# kul_rev0.net
KiCad netlist of a schematic drawn in EAGLE
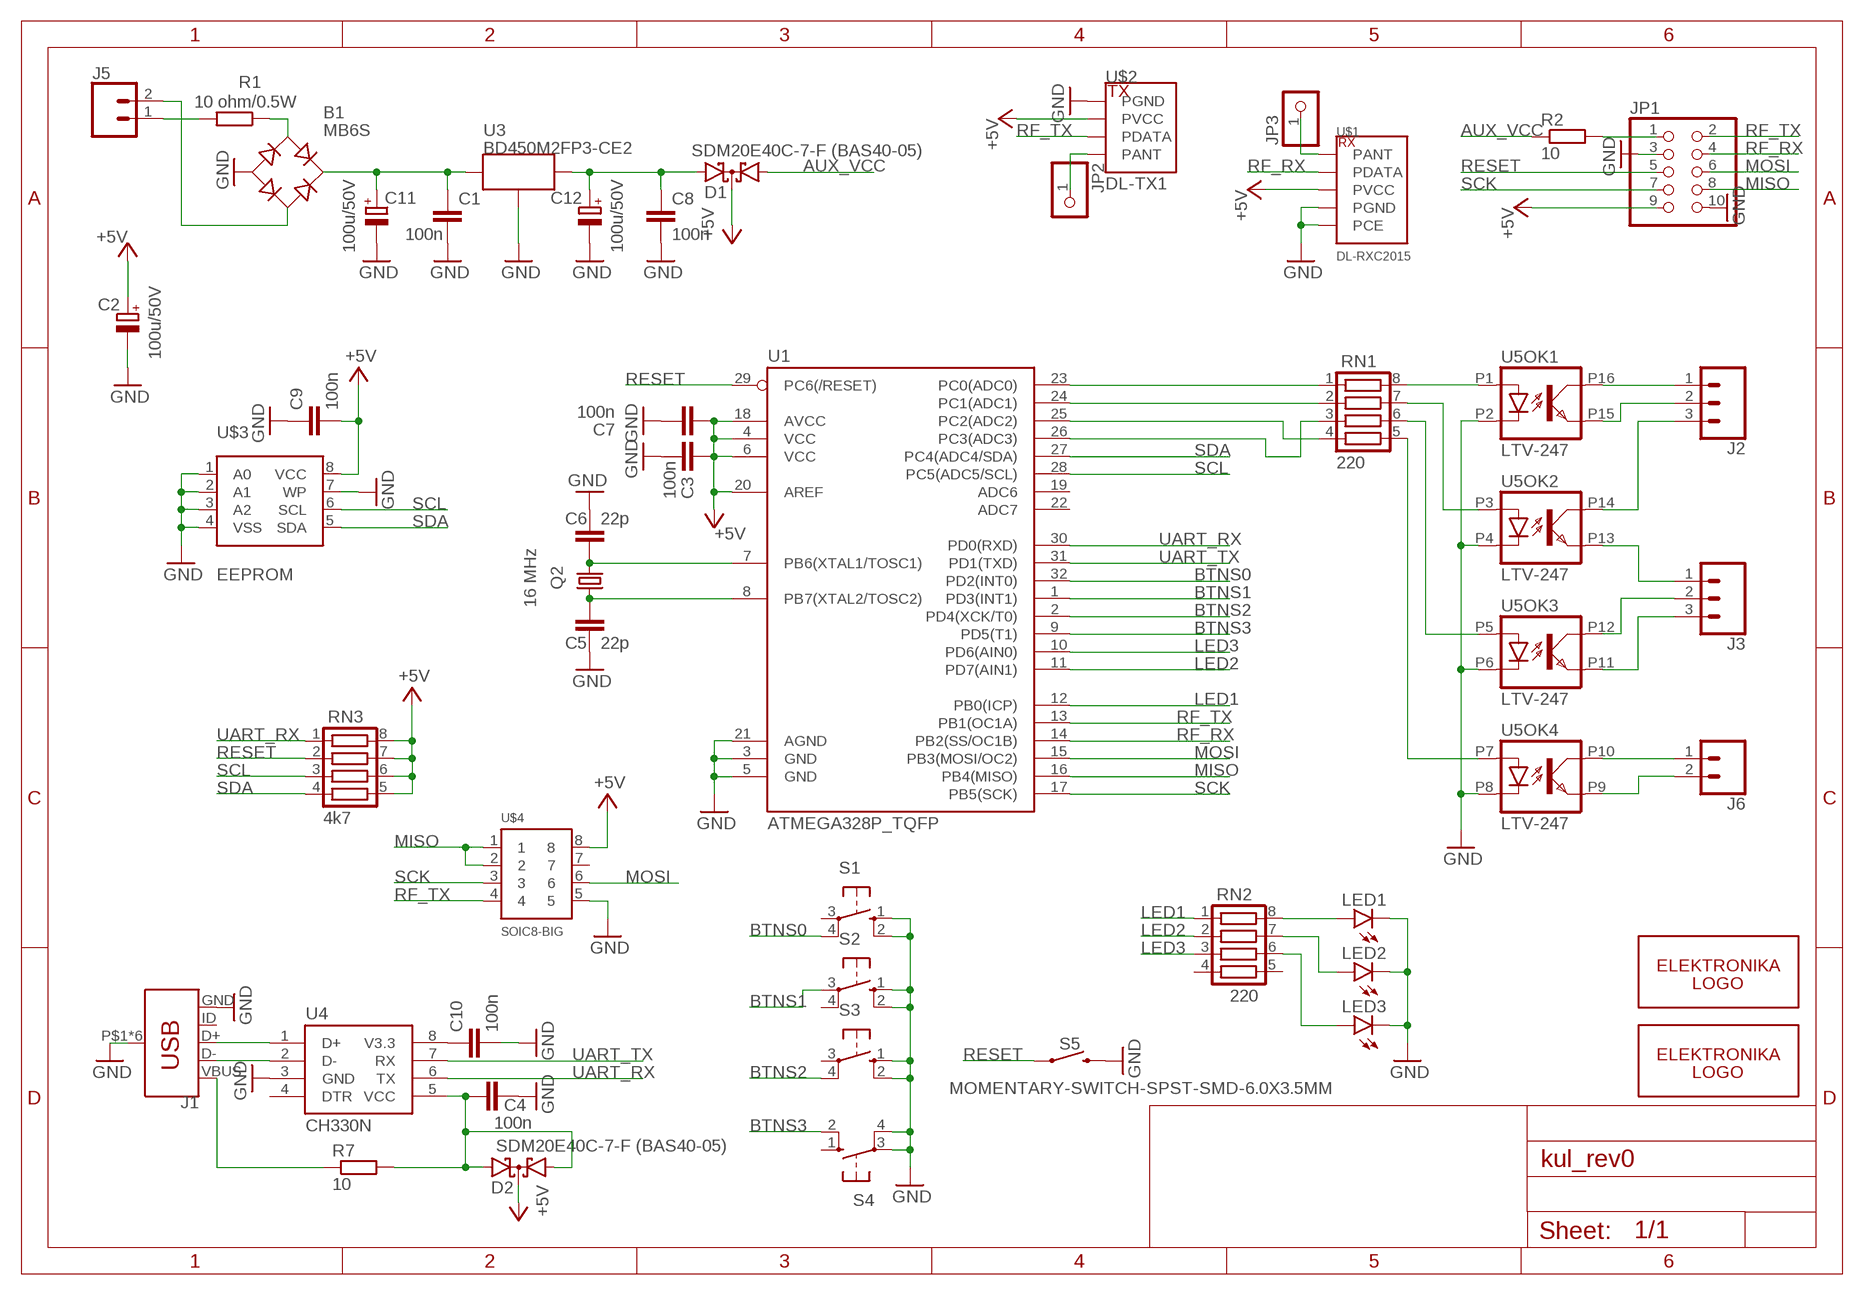
[diagram p0: schematic, sheet 1]

(export (version "E")
  (design (tool "Eeschema 10.0.6"))
  (components
    (comp (ref "B1")
      (value "MB6S")
      (footprint "eagle-import:SOIC-4")
      (libsource (lib "eagle-import") (part "MBS6"))
    )
    (comp (ref "C1")
      (value "100n")
      (footprint "eagle-import:C0603")
      (libsource (lib "eagle-import") (part "C-EUC0603"))
    )
    (comp (ref "C2")
      (value "100u/50V")
      (footprint "eagle-import:E5-6")
      (libsource (lib "eagle-import") (part "CPOL-EUE5-6"))
    )
    (comp (ref "C3")
      (value "100n")
      (footprint "eagle-import:C0603")
      (libsource (lib "eagle-import") (part "C-EUC0603"))
    )
    (comp (ref "C4")
      (value "100n")
      (footprint "eagle-import:C0603")
      (libsource (lib "eagle-import") (part "C-EUC0603"))
    )
    (comp (ref "C5")
      (value "22p")
      (footprint "eagle-import:C0603")
      (libsource (lib "eagle-import") (part "C-EUC0603"))
    )
    (comp (ref "C6")
      (value "22p")
      (footprint "eagle-import:C0603")
      (libsource (lib "eagle-import") (part "C-EUC0603"))
    )
    (comp (ref "C7")
      (value "100n")
      (footprint "eagle-import:C0603")
      (libsource (lib "eagle-import") (part "C-EUC0603"))
    )
    (comp (ref "C8")
      (value "100n")
      (footprint "eagle-import:C0603")
      (libsource (lib "eagle-import") (part "C-EUC0603"))
    )
    (comp (ref "C9")
      (value "100n")
      (footprint "eagle-import:C0603")
      (libsource (lib "eagle-import") (part "C-EUC0603"))
    )
    (comp (ref "C10")
      (value "100n")
      (footprint "eagle-import:C0603")
      (libsource (lib "eagle-import") (part "C-EUC0603"))
    )
    (comp (ref "C11")
      (value "100u/50V")
      (footprint "eagle-import:E5-6")
      (libsource (lib "eagle-import") (part "CPOL-EUE5-6"))
    )
    (comp (ref "C12")
      (value "100u/50V")
      (footprint "eagle-import:E5-6")
      (libsource (lib "eagle-import") (part "CPOL-EUE5-6"))
    )
    (comp (ref "D1")
      (value "SDM20E40C-7-F (BAS40-05)")
      (footprint "eagle-import:SOT23")
      (libsource (lib "eagle-import") (part "BAS40-05"))
    )
    (comp (ref "D2")
      (value "SDM20E40C-7-F (BAS40-05)")
      (footprint "eagle-import:SOT23")
      (libsource (lib "eagle-import") (part "BAS40-05"))
    )
    (comp (ref "J1")
      (value "USB_MICRO-BLCSC")
      (footprint "eagle-import:C40951_USB")
      (libsource (lib "eagle-import") (part "USB_MICRO-BLCSC"))
    )
    (comp (ref "J2")
      (value "CONN_03SCREW_LOCK")
      (footprint "eagle-import:SCREWTERMINAL-3.5MM-3_LOCK.007S")
      (libsource (lib "eagle-import") (part "CONN_03SCREW_LOCK"))
    )
    (comp (ref "J3")
      (value "CONN_03SCREW_LOCK")
      (footprint "eagle-import:SCREWTERMINAL-3.5MM-3_LOCK.007S")
      (libsource (lib "eagle-import") (part "CONN_03SCREW_LOCK"))
    )
    (comp (ref "J5")
      (value "CONN_023.5MM")
      (footprint "eagle-import:SCREWTERMINAL-3.5MM-2")
      (libsource (lib "eagle-import") (part "CONN_023.5MM"))
    )
    (comp (ref "J6")
      (value "CONN_023.5MM")
      (footprint "eagle-import:SCREWTERMINAL-3.5MM-2")
      (libsource (lib "eagle-import") (part "CONN_023.5MM"))
    )
    (comp (ref "JP1")
      (value "PINHD-2X5")
      (footprint "eagle-import:2X05")
      (libsource (lib "eagle-import") (part "PINHD-2X5"))
    )
    (comp (ref "JP2")
      (value "PINHD-1X1")
      (footprint "eagle-import:1X01")
      (libsource (lib "eagle-import") (part "PINHD-1X1"))
    )
    (comp (ref "JP3")
      (value "PINHD-1X1")
      (footprint "eagle-import:1X01")
      (libsource (lib "eagle-import") (part "PINHD-1X1"))
    )
    (comp (ref "LED1")
      (value "LEDCHIP-LED0805")
      (footprint "eagle-import:CHIP-LED0805")
      (libsource (lib "eagle-import") (part "LEDCHIP-LED0805"))
    )
    (comp (ref "LED2")
      (value "LEDCHIP-LED0805")
      (footprint "eagle-import:CHIP-LED0805")
      (libsource (lib "eagle-import") (part "LEDCHIP-LED0805"))
    )
    (comp (ref "LED3")
      (value "LEDCHIP-LED0805")
      (footprint "eagle-import:CHIP-LED0805")
      (libsource (lib "eagle-import") (part "LEDCHIP-LED0805"))
    )
    (comp (ref "Q2")
      (value "16 MHz")
      (footprint "eagle-import:3.2X2.5_KX-7")
      (libsource (lib "eagle-import") (part "KX-7"))
    )
    (comp (ref "R1")
      (value "10 ohm/0.5W")
      (footprint "eagle-import:R0805")
      (libsource (lib "eagle-import") (part "R-EU_R0805"))
    )
    (comp (ref "R2")
      (value "10")
      (footprint "eagle-import:R0603")
      (libsource (lib "eagle-import") (part "R-EU_R0603"))
    )
    (comp (ref "R7")
      (value "10")
      (footprint "eagle-import:R0603")
      (libsource (lib "eagle-import") (part "R-EU_R0603"))
    )
    (comp (ref "RN1")
      (value "220")
      (footprint "eagle-import:CTS742C083")
      (libsource (lib "eagle-import") (part "CTS742C083"))
    )
    (comp (ref "RN2")
      (value "220")
      (footprint "eagle-import:CTS742C083")
      (libsource (lib "eagle-import") (part "CTS742C083"))
    )
    (comp (ref "RN3")
      (value "4k7")
      (footprint "eagle-import:CTS742C083")
      (libsource (lib "eagle-import") (part "CTS742C083"))
    )
    (comp (ref "S1")
      (value "10-XX")
      (footprint "eagle-import:B3F-10XX")
      (fields (field (name "MPN") "B3F-1000"))
      (libsource (lib "eagle-import") (part "10-XX"))
    )
    (comp (ref "S2")
      (value "10-XX")
      (footprint "eagle-import:B3F-10XX")
      (fields (field (name "MPN") "B3F-1000"))
      (libsource (lib "eagle-import") (part "10-XX"))
    )
    (comp (ref "S3")
      (value "10-XX")
      (footprint "eagle-import:B3F-10XX")
      (fields (field (name "MPN") "B3F-1000"))
      (libsource (lib "eagle-import") (part "10-XX"))
    )
    (comp (ref "S4")
      (value "10-XX")
      (footprint "eagle-import:B3F-10XX")
      (fields (field (name "MPN") "B3F-1000"))
      (libsource (lib "eagle-import") (part "10-XX"))
    )
    (comp (ref "S5")
      (value "MOMENTARY-SWITCH-SPST-SMD-6.0X3.5MM")
      (footprint "eagle-import:TACTILE_SWITCH_SMD_6.0X3.5MM")
      (libsource (lib "eagle-import") (part "MOMENTARY-SWITCH-SPST-SMD-6.0X3.5MM"))
    )
    (comp (ref "U$1")
      (value "DL-RXC2015")
      (footprint "eagle-import:DL-RXC2015")
      (libsource (lib "eagle-import") (part "DL-RXC2015"))
    )
    (comp (ref "U$2")
      (value "DL-TX1")
      (footprint "eagle-import:DL-TX1")
      (libsource (lib "eagle-import") (part "DL-TX1"))
    )
    (comp (ref "U$3")
      (value "EEPROM")
      (footprint "eagle-import:SOIC8")
      (libsource (lib "eagle-import") (part "EEPROM"))
    )
    (comp (ref "U$4")
      (value "SOIC8-BIG")
      (footprint "eagle-import:SOIC8_BIG")
      (libsource (lib "eagle-import") (part "SOIC8-BIG"))
    )
    (comp (ref "U$5")
      (value "ELEKTRONIKA_BA_ELEBA_LOGO-121")
      (footprint "eagle-import:ELEKTRONIKA_BA_ELEBALOGO_ELEBALOGO_B_121")
      (libsource (lib "eagle-import") (part "ELEKTRONIKA_BA_ELEBA_LOGO-121"))
    )
    (comp (ref "U$6")
      (value "ELEKTRONIKA_BA_ELEBA_LOGO")
      (footprint "eagle-import:ELEKTRONIKA_BA_ELEBALOGO_ELEBALOGO_B_122")
      (libsource (lib "eagle-import") (part "ELEKTRONIKA_BA_ELEBA_LOGO"))
    )
    (comp (ref "U1")
      (value "ATMEGA328P_TQFP")
      (footprint "eagle-import:TQFP32-08")
      (libsource (lib "eagle-import") (part "ATMEGA328P_TQFP"))
    )
    (comp (ref "U3")
      (value "BD450M2FP3-CE2")
      (footprint "eagle-import:C308597_LDO")
      (libsource (lib "eagle-import") (part "C308597_LDO"))
    )
    (comp (ref "U4")
      (value "CH330N")
      (footprint "eagle-import:SOIC8")
      (libsource (lib "eagle-import") (part "CH330N"))
    )
    (comp (ref "U5")
      (value "LTV-247")
      (footprint "eagle-import:SOP-16_4.4MM")
      (libsource (lib "eagle-import") (part "LTV-247"))
    )
  )
  (nets
    (net (code "1") (name "+5V") (class "Default")
      (node (ref "C2") (pin "+") (pinfunction "+_+") (pintype "passive"))
      (node (ref "C3") (pin "2") (pinfunction "2_2") (pintype "passive"))
      (node (ref "C7") (pin "2") (pinfunction "2_2") (pintype "passive"))
      (node (ref "C9") (pin "2") (pinfunction "2_2") (pintype "passive"))
      (node (ref "D1") (pin "3") (pinfunction "C_3") (pintype "passive"))
      (node (ref "D2") (pin "3") (pinfunction "C_3") (pintype "passive"))
      (node (ref "JP1") (pin "9") (pinfunction "9_9") (pintype "passive"))
      (node (ref "RN3") (pin "5") (pinfunction "5_5") (pintype "passive"))
      (node (ref "RN3") (pin "6") (pinfunction "6_6") (pintype "passive"))
      (node (ref "RN3") (pin "7") (pinfunction "7_7") (pintype "passive"))
      (node (ref "RN3") (pin "8") (pinfunction "8_8") (pintype "passive"))
      (node (ref "U$1") (pin "PVCC") (pinfunction "PVCC_PVCC") (pintype "power_in"))
      (node (ref "U$2") (pin "PVDD") (pinfunction "PVCC_PVDD") (pintype "power_in"))
      (node (ref "U$3") (pin "8") (pinfunction "VCC_8") (pintype "bidirectional"))
      (node (ref "U$4") (pin "8") (pinfunction "8_8") (pintype "bidirectional"))
      (node (ref "U1") (pin "18") (pinfunction "AVCC_18") (pintype "bidirectional"))
      (node (ref "U1") (pin "20") (pinfunction "AREF_20") (pintype "bidirectional"))
      (node (ref "U1") (pin "4") (pinfunction "VCC_4") (pintype "bidirectional"))
      (node (ref "U1") (pin "6") (pinfunction "VCC_6") (pintype "bidirectional"))
    )
    (net (code "2") (name "/AUX_VCC") (class "Default")
      (node (ref "D1") (pin "1") (pinfunction "A1_1") (pintype "passive"))
      (node (ref "R2") (pin "1") (pinfunction "1_1") (pintype "passive"))
    )
    (net (code "3") (name "/BTNS0") (class "Default")
      (node (ref "S1") (pin "4") (pinfunction "P1_4") (pintype "passive"))
      (node (ref "U1") (pin "32") (pinfunction "PD2(INT0)_32") (pintype "bidirectional"))
    )
    (net (code "4") (name "/BTNS1") (class "Default")
      (node (ref "S2") (pin "3") (pinfunction "P_3") (pintype "passive"))
      (node (ref "U1") (pin "1") (pinfunction "PD3(INT1)_1") (pintype "bidirectional"))
    )
    (net (code "5") (name "/BTNS2") (class "Default")
      (node (ref "S3") (pin "4") (pinfunction "P1_4") (pintype "passive"))
      (node (ref "U1") (pin "2") (pinfunction "PD4(XCK/T0)_2") (pintype "bidirectional"))
    )
    (net (code "6") (name "/BTNS3") (class "Default")
      (node (ref "S4") (pin "2") (pinfunction "S1_2") (pintype "passive"))
      (node (ref "U1") (pin "9") (pinfunction "PD5(T1)_9") (pintype "bidirectional"))
    )
    (net (code "7") (name "/LED1") (class "Default")
      (node (ref "RN2") (pin "1") (pinfunction "1_1") (pintype "passive"))
      (node (ref "U1") (pin "12") (pinfunction "PB0(ICP)_12") (pintype "bidirectional"))
    )
    (net (code "8") (name "/LED2") (class "Default")
      (node (ref "RN2") (pin "2") (pinfunction "2_2") (pintype "passive"))
      (node (ref "U1") (pin "11") (pinfunction "PD7(AIN1)_11") (pintype "bidirectional"))
    )
    (net (code "9") (name "/LED3") (class "Default")
      (node (ref "RN2") (pin "3") (pinfunction "3_3") (pintype "passive"))
      (node (ref "U1") (pin "10") (pinfunction "PD6(AIN0)_10") (pintype "bidirectional"))
    )
    (net (code "10") (name "/MISO") (class "Default")
      (node (ref "JP1") (pin "8") (pinfunction "8_8") (pintype "passive"))
      (node (ref "U$4") (pin "1") (pinfunction "1_1") (pintype "bidirectional"))
      (node (ref "U$4") (pin "2") (pinfunction "2_2") (pintype "bidirectional"))
      (node (ref "U1") (pin "16") (pinfunction "PB4(MISO)_16") (pintype "bidirectional"))
    )
    (net (code "11") (name "/MOSI") (class "Default")
      (node (ref "JP1") (pin "6") (pinfunction "6_6") (pintype "passive"))
      (node (ref "U$4") (pin "6") (pinfunction "6_6") (pintype "bidirectional"))
      (node (ref "U1") (pin "15") (pinfunction "PB3(MOSI/OC2)_15") (pintype "bidirectional"))
    )
    (net (code "12") (name "/RESET") (class "Default")
      (node (ref "JP1") (pin "5") (pinfunction "5_5") (pintype "passive"))
      (node (ref "RN3") (pin "2") (pinfunction "2_2") (pintype "passive"))
      (node (ref "S5") (pin "1") (pinfunction "1_1") (pintype "passive"))
      (node (ref "U1") (pin "29") (pinfunction "PC6(/RESET)_29") (pintype "bidirectional"))
    )
    (net (code "13") (name "/RF_RX") (class "Default")
      (node (ref "JP1") (pin "4") (pinfunction "4_4") (pintype "passive"))
      (node (ref "U$1") (pin "PDATA") (pinfunction "PDATA_PDATA") (pintype "output"))
      (node (ref "U1") (pin "14") (pinfunction "PB2(SS/OC1B)_14") (pintype "bidirectional"))
    )
    (net (code "14") (name "/RF_TX") (class "Default")
      (node (ref "JP1") (pin "2") (pinfunction "2_2") (pintype "passive"))
      (node (ref "U$2") (pin "PDATA") (pinfunction "PDATA_PDATA") (pintype "input"))
      (node (ref "U$4") (pin "4") (pinfunction "4_4") (pintype "bidirectional"))
      (node (ref "U1") (pin "13") (pinfunction "PB1(OC1A)_13") (pintype "bidirectional"))
    )
    (net (code "15") (name "/SCK") (class "Default")
      (node (ref "JP1") (pin "7") (pinfunction "7_7") (pintype "passive"))
      (node (ref "U$4") (pin "3") (pinfunction "3_3") (pintype "bidirectional"))
      (node (ref "U1") (pin "17") (pinfunction "PB5(SCK)_17") (pintype "bidirectional"))
    )
    (net (code "16") (name "/SCL") (class "Default")
      (node (ref "RN3") (pin "3") (pinfunction "3_3") (pintype "passive"))
      (node (ref "U$3") (pin "6") (pinfunction "SCL_6") (pintype "bidirectional"))
      (node (ref "U1") (pin "28") (pinfunction "PC5(ADC5/SCL)_28") (pintype "bidirectional"))
    )
    (net (code "17") (name "/SDA") (class "Default")
      (node (ref "RN3") (pin "4") (pinfunction "4_4") (pintype "passive"))
      (node (ref "U$3") (pin "5") (pinfunction "SDA_5") (pintype "bidirectional"))
      (node (ref "U1") (pin "27") (pinfunction "PC4(ADC4/SDA)_27") (pintype "bidirectional"))
    )
    (net (code "18") (name "/UART_RX") (class "Default")
      (node (ref "RN3") (pin "1") (pinfunction "1_1") (pintype "passive"))
      (node (ref "U1") (pin "30") (pinfunction "PD0(RXD)_30") (pintype "bidirectional"))
      (node (ref "U4") (pin "6") (pinfunction "TX_6") (pintype "output"))
    )
    (net (code "19") (name "/UART_TX") (class "Default")
      (node (ref "U1") (pin "31") (pinfunction "PD1(TXD)_31") (pintype "bidirectional"))
      (node (ref "U4") (pin "7") (pinfunction "RX_7") (pintype "input"))
    )
    (net (code "20") (name "GND") (class "Default")
      (node (ref "B1") (pin "-") (pinfunction "-_-") (pintype "passive"))
      (node (ref "C1") (pin "2") (pinfunction "2_2") (pintype "passive"))
      (node (ref "C10") (pin "2") (pinfunction "2_2") (pintype "passive"))
      (node (ref "C11") (pin "-") (pinfunction "-_-") (pintype "passive"))
      (node (ref "C12") (pin "-") (pinfunction "-_-") (pintype "passive"))
      (node (ref "C2") (pin "-") (pinfunction "-_-") (pintype "passive"))
      (node (ref "C3") (pin "1") (pinfunction "1_1") (pintype "passive"))
      (node (ref "C4") (pin "2") (pinfunction "2_2") (pintype "passive"))
      (node (ref "C5") (pin "2") (pinfunction "2_2") (pintype "passive"))
      (node (ref "C6") (pin "1") (pinfunction "1_1") (pintype "passive"))
      (node (ref "C7") (pin "1") (pinfunction "1_1") (pintype "passive"))
      (node (ref "C8") (pin "2") (pinfunction "2_2") (pintype "passive"))
      (node (ref "C9") (pin "1") (pinfunction "1_1") (pintype "passive"))
      (node (ref "J1") (pin "GND") (pinfunction "GND_GND") (pintype "power_in"))
      (node (ref "J1") (pin "P$1") (pinfunction "SHIELD_P$1") (pintype "bidirectional"))
      (node (ref "J1") (pin "P$2") (pinfunction "SHIELD_P$2") (pintype "bidirectional"))
      (node (ref "J1") (pin "P$3") (pinfunction "SHIELD_P$3") (pintype "bidirectional"))
      (node (ref "J1") (pin "P$4") (pinfunction "SHIELD_P$4") (pintype "bidirectional"))
      (node (ref "J1") (pin "SHIELD1") (pinfunction "SHIELD_SHIELD1") (pintype "bidirectional"))
      (node (ref "J1") (pin "SHIELD2") (pinfunction "SHIELD_SHIELD2") (pintype "bidirectional"))
      (node (ref "JP1") (pin "10") (pinfunction "10_10") (pintype "passive"))
      (node (ref "JP1") (pin "3") (pinfunction "3_3") (pintype "passive"))
      (node (ref "LED1") (pin "C") (pinfunction "C_C") (pintype "passive"))
      (node (ref "LED2") (pin "C") (pinfunction "C_C") (pintype "passive"))
      (node (ref "LED3") (pin "C") (pinfunction "C_C") (pintype "passive"))
      (node (ref "S1") (pin "1") (pinfunction "S_1") (pintype "passive"))
      (node (ref "S1") (pin "2") (pinfunction "S1_2") (pintype "passive"))
      (node (ref "S2") (pin "1") (pinfunction "S_1") (pintype "passive"))
      (node (ref "S2") (pin "2") (pinfunction "S1_2") (pintype "passive"))
      (node (ref "S3") (pin "1") (pinfunction "S_1") (pintype "passive"))
      (node (ref "S3") (pin "2") (pinfunction "S1_2") (pintype "passive"))
      (node (ref "S4") (pin "3") (pinfunction "P_3") (pintype "passive"))
      (node (ref "S4") (pin "4") (pinfunction "P1_4") (pintype "passive"))
      (node (ref "S5") (pin "2") (pinfunction "2_2") (pintype "passive"))
      (node (ref "U$1") (pin "PCE") (pinfunction "PCE_PCE") (pintype "input"))
      (node (ref "U$1") (pin "PGND1") (pinfunction "PGND_PGND1") (pintype "power_in"))
      (node (ref "U$1") (pin "PGND2") (pinfunction "PGND_PGND2") (pintype "power_in"))
      (node (ref "U$2") (pin "PGND") (pinfunction "PGND_PGND") (pintype "power_in"))
      (node (ref "U$3") (pin "1") (pinfunction "A0_1") (pintype "bidirectional"))
      (node (ref "U$3") (pin "2") (pinfunction "A1_2") (pintype "bidirectional"))
      (node (ref "U$3") (pin "3") (pinfunction "A2_3") (pintype "bidirectional"))
      (node (ref "U$3") (pin "4") (pinfunction "VSS_4") (pintype "bidirectional"))
      (node (ref "U$3") (pin "7") (pinfunction "WP_7") (pintype "bidirectional"))
      (node (ref "U$4") (pin "5") (pinfunction "5_5") (pintype "bidirectional"))
      (node (ref "U1") (pin "21") (pinfunction "AGND_21") (pintype "bidirectional"))
      (node (ref "U1") (pin "3") (pinfunction "GND_3") (pintype "bidirectional"))
      (node (ref "U1") (pin "5") (pinfunction "GND_5") (pintype "bidirectional"))
      (node (ref "U3") (pin "PGND1") (pinfunction "PGND_PGND1") (pintype "power_in"))
      (node (ref "U3") (pin "PGND2") (pinfunction "PGND_PGND2") (pintype "power_in"))
      (node (ref "U4") (pin "3") (pinfunction "GND_3") (pintype "power_in"))
      (node (ref "U5") (pin "P2") (pinfunction "C_P2") (pintype "passive"))
      (node (ref "U5") (pin "P4") (pinfunction "C_P4") (pintype "passive"))
      (node (ref "U5") (pin "P6") (pinfunction "C_P6") (pintype "passive"))
      (node (ref "U5") (pin "P8") (pinfunction "C_P8") (pintype "passive"))
    )
    (net (code "21") (name "Net-(B1-AC1)") (class "Default")
      (node (ref "B1") (pin "~1") (pinfunction "AC1_~1") (pintype "passive"))
      (node (ref "R1") (pin "1") (pinfunction "1_1") (pintype "passive"))
    )
    (net (code "22") (name "Net-(B1-AC2)") (class "Default")
      (node (ref "B1") (pin "~2") (pinfunction "AC2_~2") (pintype "passive"))
      (node (ref "J5") (pin "2") (pinfunction "2_2") (pintype "passive"))
    )
    (net (code "23") (name "Net-(B1-Pad+)") (class "Default")
      (node (ref "B1") (pin "+") (pinfunction "+_+") (pintype "passive"))
      (node (ref "C1") (pin "1") (pinfunction "1_1") (pintype "passive"))
      (node (ref "C11") (pin "+") (pinfunction "+_+") (pintype "passive"))
      (node (ref "U3") (pin "PIN") (pinfunction "PIN_PIN") (pintype "power_in"))
    )
    (net (code "24") (name "Net-(D1-A2)") (class "Default")
      (node (ref "C12") (pin "+") (pinfunction "+_+") (pintype "passive"))
      (node (ref "C8") (pin "1") (pinfunction "1_1") (pintype "passive"))
      (node (ref "D1") (pin "2") (pinfunction "A2_2") (pintype "passive"))
      (node (ref "U3") (pin "POUT") (pinfunction "POUT_POUT") (pintype "power_in"))
    )
    (net (code "25") (name "Net-(D2-A1)") (class "Default")
      (node (ref "C4") (pin "1") (pinfunction "1_1") (pintype "passive"))
      (node (ref "D2") (pin "1") (pinfunction "A1_1") (pintype "passive"))
      (node (ref "D2") (pin "2") (pinfunction "A2_2") (pintype "passive"))
      (node (ref "R7") (pin "2") (pinfunction "2_2") (pintype "passive"))
      (node (ref "U4") (pin "5") (pinfunction "VCC_5") (pintype "power_in"))
    )
    (net (code "26") (name "Net-(J1-PadVBUS)") (class "Default")
      (node (ref "J1") (pin "VBUS") (pinfunction "VBUS_VBUS") (pintype "power_in"))
      (node (ref "R7") (pin "1") (pinfunction "1_1") (pintype "passive"))
    )
    (net (code "27") (name "Net-(J5-Pad1)") (class "Default")
      (node (ref "J5") (pin "1") (pinfunction "1_1") (pintype "passive"))
      (node (ref "R1") (pin "2") (pinfunction "2_2") (pintype "passive"))
    )
    (net (code "28") (name "Net-(JP1-Pad1)") (class "Default")
      (node (ref "JP1") (pin "1") (pinfunction "1_1") (pintype "passive"))
      (node (ref "R2") (pin "2") (pinfunction "2_2") (pintype "passive"))
    )
    (net (code "29") (name "Net-(JP2-Pad1)") (class "Default")
      (node (ref "JP2") (pin "1") (pinfunction "1_1") (pintype "passive"))
      (node (ref "U$2") (pin "PANT") (pinfunction "PANT_PANT") (pintype "output"))
    )
    (net (code "30") (name "Net-(JP3-Pad1)") (class "Default")
      (node (ref "JP3") (pin "1") (pinfunction "1_1") (pintype "passive"))
      (node (ref "U$1") (pin "PANT") (pinfunction "PANT_PANT") (pintype "input"))
    )
    (net (code "31") (name "Net-(LED1-PadA)") (class "Default")
      (node (ref "LED1") (pin "A") (pinfunction "A_A") (pintype "passive"))
      (node (ref "RN2") (pin "8") (pinfunction "8_8") (pintype "passive"))
    )
    (net (code "32") (name "Net-(LED2-PadA)") (class "Default")
      (node (ref "LED2") (pin "A") (pinfunction "A_A") (pintype "passive"))
      (node (ref "RN2") (pin "7") (pinfunction "7_7") (pintype "passive"))
    )
    (net (code "33") (name "Net-(LED3-PadA)") (class "Default")
      (node (ref "LED3") (pin "A") (pinfunction "A_A") (pintype "passive"))
      (node (ref "RN2") (pin "6") (pinfunction "6_6") (pintype "passive"))
    )
    (net (code "34") (name "Net-(Q2-2)") (class "Default")
      (node (ref "C6") (pin "2") (pinfunction "2_2") (pintype "passive"))
      (node (ref "Q2") (pin "3") (pinfunction "2_3") (pintype "passive"))
      (node (ref "U1") (pin "7") (pinfunction "PB6(XTAL1/TOSC1)_7") (pintype "bidirectional"))
    )
    (net (code "35") (name "Net-(U1-PB7(XTAL2{slash}TOSC2))") (class "Default")
      (node (ref "C5") (pin "1") (pinfunction "1_1") (pintype "passive"))
      (node (ref "Q2") (pin "1") (pinfunction "1_1") (pintype "passive"))
      (node (ref "U1") (pin "8") (pinfunction "PB7(XTAL2/TOSC2)_8") (pintype "bidirectional"))
    )
    (net (code "36") (name "Net-(U1-PC0(ADC0))") (class "Default")
      (node (ref "RN1") (pin "1") (pinfunction "1_1") (pintype "passive"))
      (node (ref "U1") (pin "23") (pinfunction "PC0(ADC0)_23") (pintype "bidirectional"))
    )
    (net (code "37") (name "Net-(U1-PC1(ADC1))") (class "Default")
      (node (ref "RN1") (pin "2") (pinfunction "2_2") (pintype "passive"))
      (node (ref "U1") (pin "24") (pinfunction "PC1(ADC1)_24") (pintype "bidirectional"))
    )
    (net (code "38") (name "Net-(U1-PC2(ADC2))") (class "Default")
      (node (ref "RN1") (pin "4") (pinfunction "4_4") (pintype "passive"))
      (node (ref "U1") (pin "25") (pinfunction "PC2(ADC2)_25") (pintype "bidirectional"))
    )
    (net (code "39") (name "Net-(U1-PC3(ADC3))") (class "Default")
      (node (ref "RN1") (pin "3") (pinfunction "3_3") (pintype "passive"))
      (node (ref "U1") (pin "26") (pinfunction "PC3(ADC3)_26") (pintype "bidirectional"))
    )
    (net (code "40") (name "Net-(U4-D+)") (class "Default")
      (node (ref "J1") (pin "D+") (pinfunction "D+_D+") (pintype "bidirectional"))
      (node (ref "U4") (pin "1") (pinfunction "D+_1") (pintype "bidirectional"))
    )
    (net (code "41") (name "Net-(U4-D-)") (class "Default")
      (node (ref "J1") (pin "D-") (pinfunction "D-_D-") (pintype "bidirectional"))
      (node (ref "U4") (pin "2") (pinfunction "D-_2") (pintype "bidirectional"))
    )
    (net (code "42") (name "Net-(U4-V3.3)") (class "Default")
      (node (ref "C10") (pin "1") (pinfunction "1_1") (pintype "passive"))
      (node (ref "U4") (pin "8") (pinfunction "V3.3_8") (pintype "power_in"))
    )
    (net (code "43") (name "Net-(U5A-A)") (class "Default")
      (node (ref "RN1") (pin "8") (pinfunction "8_8") (pintype "passive"))
      (node (ref "U5") (pin "P1") (pinfunction "A_P1") (pintype "passive"))
    )
    (net (code "44") (name "Net-(U5A-COL)") (class "Default")
      (node (ref "J2") (pin "1") (pinfunction "1_1") (pintype "passive"))
      (node (ref "U5") (pin "P16") (pinfunction "COL_P16") (pintype "passive"))
    )
    (net (code "45") (name "Net-(U5A-EMIT)") (class "Default")
      (node (ref "J2") (pin "2") (pinfunction "2_2") (pintype "passive"))
      (node (ref "U5") (pin "P15") (pinfunction "EMIT_P15") (pintype "passive"))
    )
    (net (code "46") (name "Net-(U5B-A)") (class "Default")
      (node (ref "RN1") (pin "7") (pinfunction "7_7") (pintype "passive"))
      (node (ref "U5") (pin "P3") (pinfunction "A_P3") (pintype "passive"))
    )
    (net (code "47") (name "Net-(U5B-COL)") (class "Default")
      (node (ref "J2") (pin "3") (pinfunction "3_3") (pintype "passive"))
      (node (ref "U5") (pin "P14") (pinfunction "COL_P14") (pintype "passive"))
    )
    (net (code "48") (name "Net-(U5B-EMIT)") (class "Default")
      (node (ref "J3") (pin "1") (pinfunction "1_1") (pintype "passive"))
      (node (ref "U5") (pin "P13") (pinfunction "EMIT_P13") (pintype "passive"))
    )
    (net (code "49") (name "Net-(U5C-A)") (class "Default")
      (node (ref "RN1") (pin "6") (pinfunction "6_6") (pintype "passive"))
      (node (ref "U5") (pin "P5") (pinfunction "A_P5") (pintype "passive"))
    )
    (net (code "50") (name "Net-(U5C-COL)") (class "Default")
      (node (ref "J3") (pin "2") (pinfunction "2_2") (pintype "passive"))
      (node (ref "U5") (pin "P12") (pinfunction "COL_P12") (pintype "passive"))
    )
    (net (code "51") (name "Net-(U5C-EMIT)") (class "Default")
      (node (ref "J3") (pin "3") (pinfunction "3_3") (pintype "passive"))
      (node (ref "U5") (pin "P11") (pinfunction "EMIT_P11") (pintype "passive"))
    )
    (net (code "52") (name "Net-(U5D-A)") (class "Default")
      (node (ref "RN1") (pin "5") (pinfunction "5_5") (pintype "passive"))
      (node (ref "U5") (pin "P7") (pinfunction "A_P7") (pintype "passive"))
    )
    (net (code "53") (name "Net-(U5D-COL)") (class "Default")
      (node (ref "J6") (pin "1") (pinfunction "1_1") (pintype "passive"))
      (node (ref "U5") (pin "P10") (pinfunction "COL_P10") (pintype "passive"))
    )
    (net (code "54") (name "Net-(U5D-EMIT)") (class "Default")
      (node (ref "J6") (pin "2") (pinfunction "2_2") (pintype "passive"))
      (node (ref "U5") (pin "P9") (pinfunction "EMIT_P9") (pintype "passive"))
    )
    (net (code "55") (name "unconnected-(J1-PadID)") (class "Default")
      (node (ref "J1") (pin "ID") (pinfunction "ID_ID") (pintype "bidirectional"))
    )
    (net (code "56") (name "unconnected-(RN2-Pad4)") (class "Default")
      (node (ref "RN2") (pin "4") (pinfunction "4_4") (pintype "passive"))
    )
    (net (code "57") (name "unconnected-(RN2-Pad5)") (class "Default")
      (node (ref "RN2") (pin "5") (pinfunction "5_5") (pintype "passive"))
    )
    (net (code "58") (name "unconnected-(S1-P-Pad3)") (class "Default")
      (node (ref "S1") (pin "3") (pinfunction "P_3") (pintype "passive"))
    )
    (net (code "59") (name "unconnected-(S2-P1-Pad4)") (class "Default")
      (node (ref "S2") (pin "4") (pinfunction "P1_4") (pintype "passive"))
    )
    (net (code "60") (name "unconnected-(S3-P-Pad3)") (class "Default")
      (node (ref "S3") (pin "3") (pinfunction "P_3") (pintype "passive"))
    )
    (net (code "61") (name "unconnected-(S4-S-Pad1)") (class "Default")
      (node (ref "S4") (pin "1") (pinfunction "S_1") (pintype "passive"))
    )
    (net (code "62") (name "unconnected-(U$4-Pad7)") (class "Default")
      (node (ref "U$4") (pin "7") (pinfunction "7_7") (pintype "bidirectional"))
    )
    (net (code "63") (name "unconnected-(U1-ADC6-Pad19)") (class "Default")
      (node (ref "U1") (pin "19") (pinfunction "ADC6_19") (pintype "bidirectional"))
    )
    (net (code "64") (name "unconnected-(U1-ADC7-Pad22)") (class "Default")
      (node (ref "U1") (pin "22") (pinfunction "ADC7_22") (pintype "bidirectional"))
    )
    (net (code "65") (name "unconnected-(U4-DTR-Pad4)") (class "Default")
      (node (ref "U4") (pin "4") (pinfunction "DTR_4") (pintype "bidirectional"))
    )
  )
)
